# SAST_PCB_V2B_Test_Beta_Sensors.net
KiCad netlist of a schematic drawn in Altium Designer
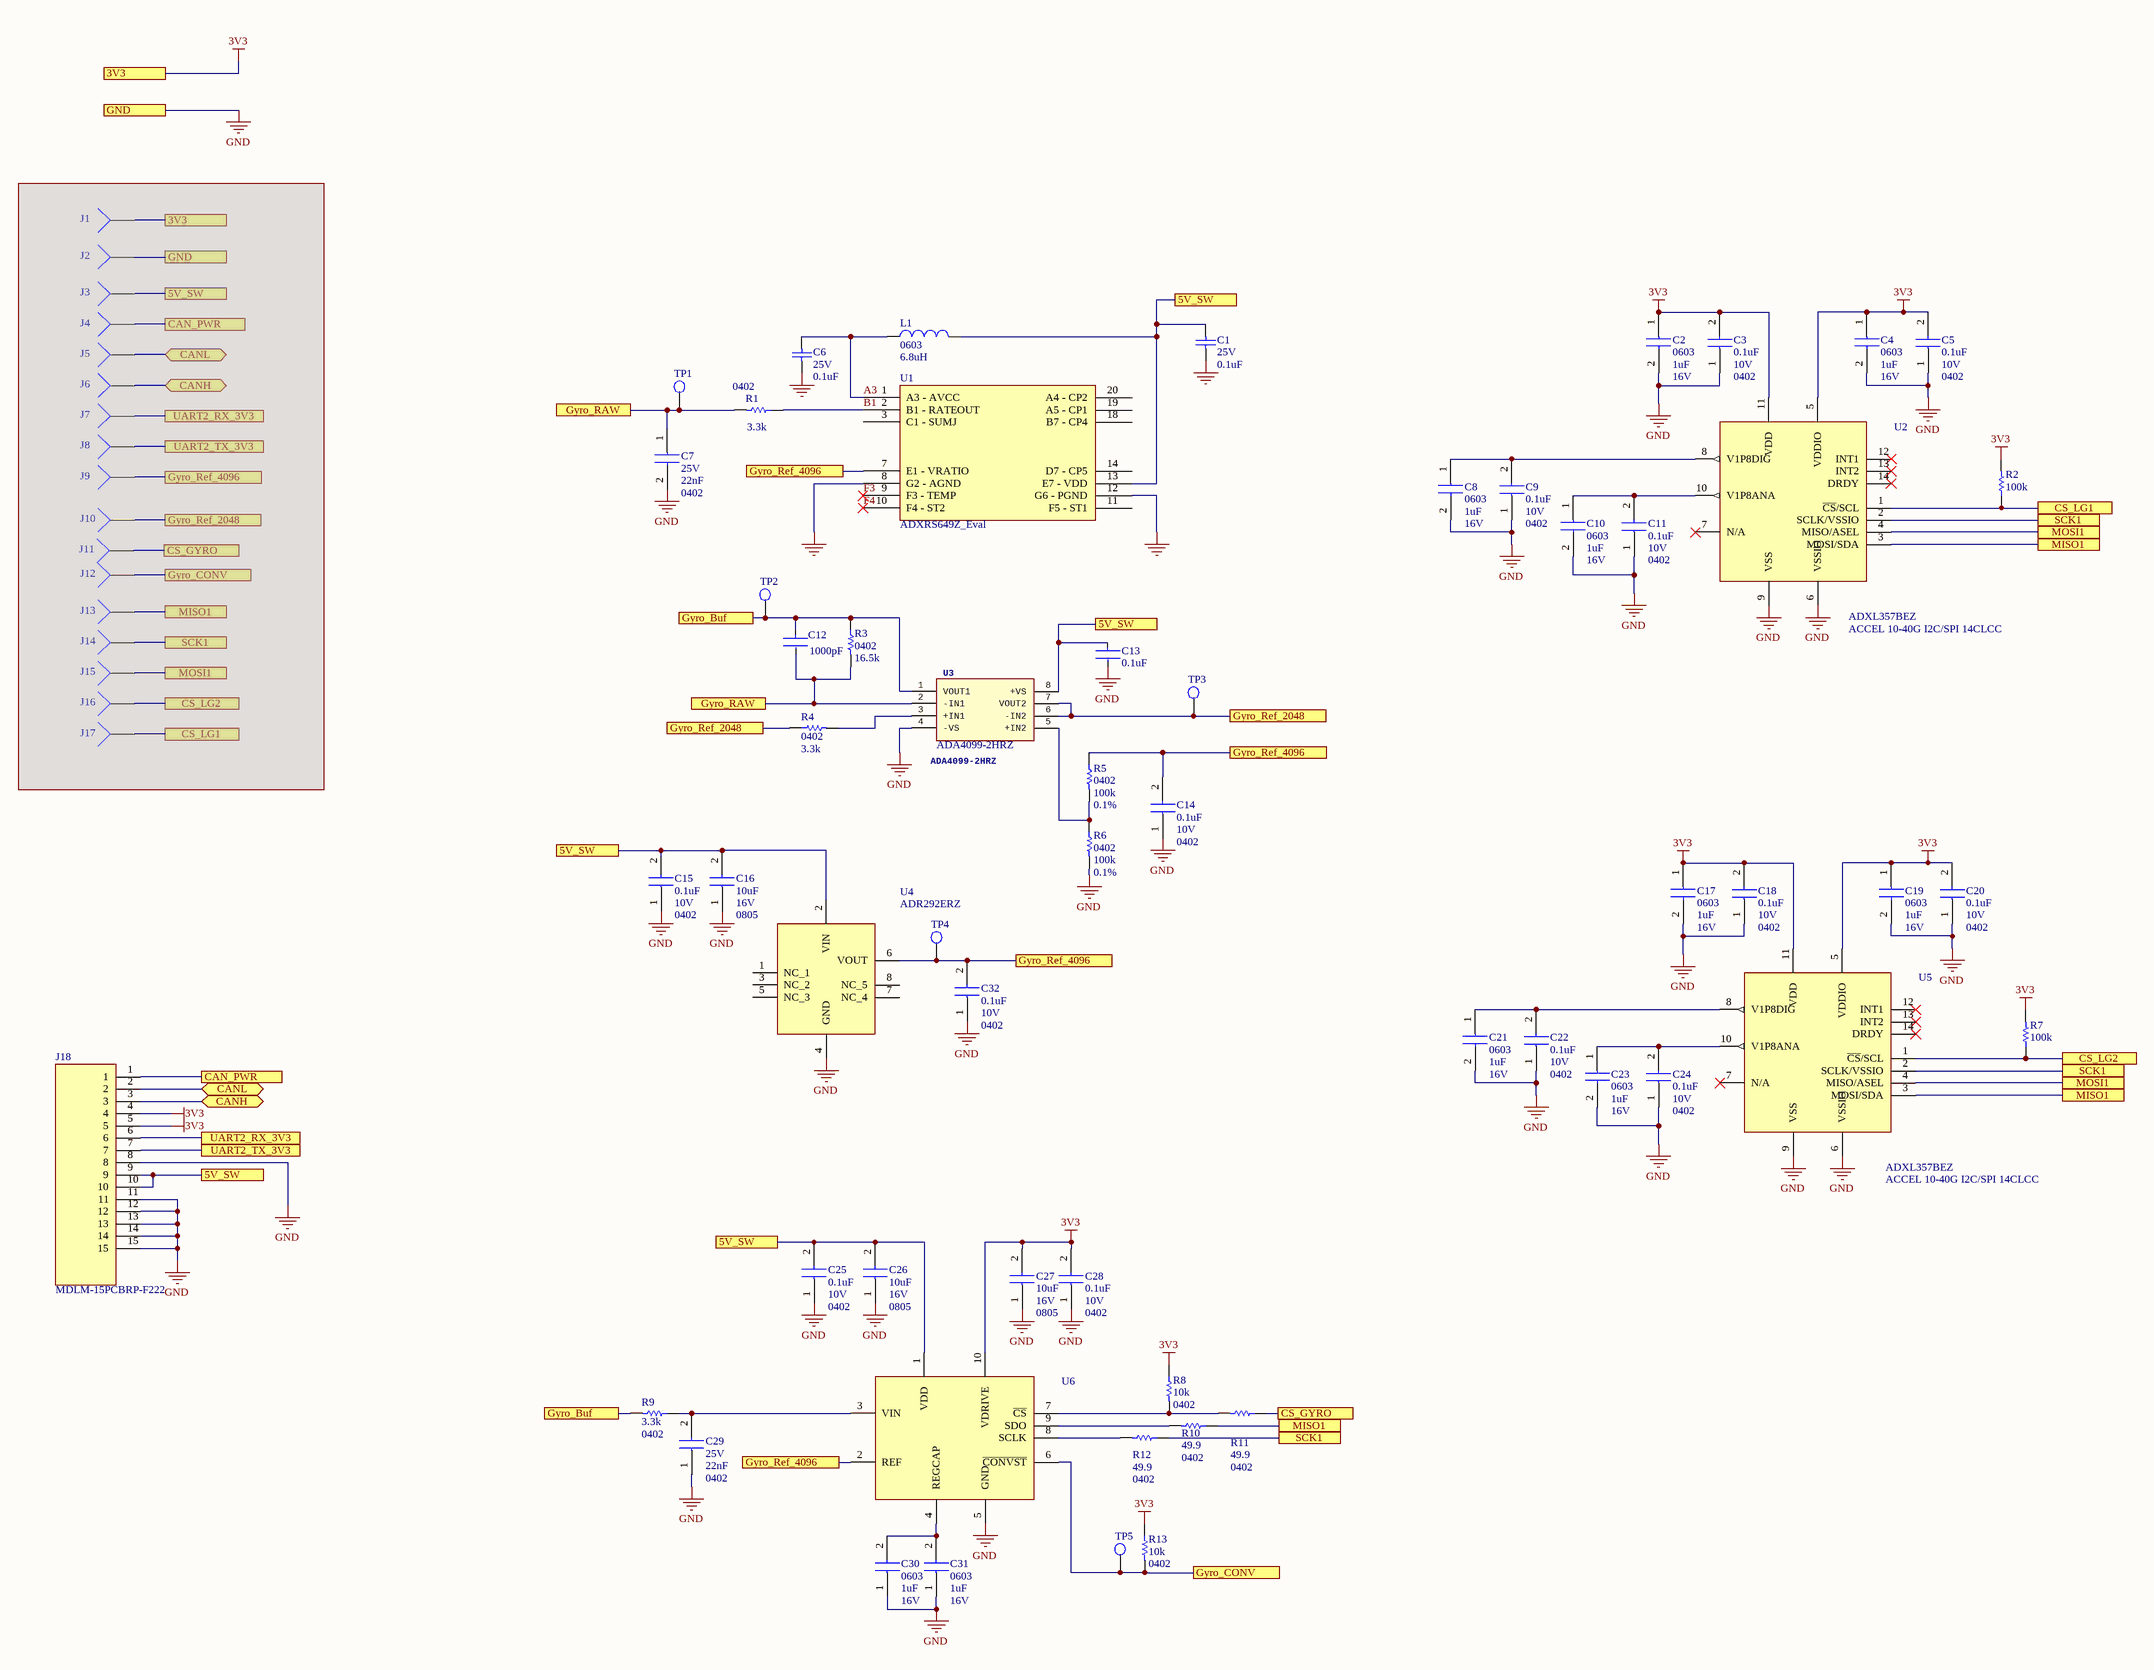
[diagram p0: SAST_PCB_V2B_Test_Beta_Sensors.SchDoc]

(export (version "E")
  (design (tool "Eeschema 10.0.6"))
  (components
    (comp (ref "C1")
      (value "25V")
      (footprint "0402_DSP")
      (description "Capacitor")
      (fields (field (name "ALTIUM_VALUE") "0.1uF") (field (name "PUBLISHER") "Altium Limited"))
      (libsource (lib "Miscellaneous Devices") (part "Cap"))
    )
    (comp (ref "C2")
      (value "1uF")
      (footprint "0603_DSP")
      (description "Capacitor: 1 µF ±10% 16V Ceramic Capacitor X8L 0603")
      (fields
        (field (name "MANUFACTURER_PART_NUMBER") "GCG188L8EE105KA07D")
        (field (name "MOUSER PART NUMBER") "81-GCG188L8EE105KA7D")
        (field (name "CASE/PACKAGE") "0603")
        (field (name "VOLTAGE") "16V")
      )
      (libsource (lib "CS_Library") (part "GCG188L8EE105KA07D"))
    )
    (comp (ref "C3")
      (value "0.1uF")
      (footprint "0402_DSP")
      (description "Capacitor: 0.1 µF ±10% 10V Ceramic Capacitor X8M 0201")
      (fields
        (field (name "MANUFACTURER_PART_NUMBER") "GCM033M8ED104KE07J")
        (field (name "MOUSER PART NUMBER") "81-GCM033M8ED104KE07")
        (field (name "VOLTAGE") "10V")
        (field (name "CASE/PACKAGE") "0402")
      )
      (libsource (lib "CS_Library") (part "GCM033M8ED104KE07J"))
    )
    (comp (ref "C4")
      (value "1uF")
      (footprint "0603_DSP")
      (description "Capacitor: 1 µF ±10% 16V Ceramic Capacitor X8L 0603")
      (fields
        (field (name "MANUFACTURER_PART_NUMBER") "GCG188L8EE105KA07D")
        (field (name "MOUSER PART NUMBER") "81-GCG188L8EE105KA7D")
        (field (name "CASE/PACKAGE") "0603")
        (field (name "VOLTAGE") "16V")
      )
      (libsource (lib "CS_Library") (part "GCG188L8EE105KA07D"))
    )
    (comp (ref "C5")
      (value "0.1uF")
      (footprint "0402_DSP")
      (description "Capacitor: 0.1 µF ±10% 10V Ceramic Capacitor X8M 0201")
      (fields
        (field (name "MANUFACTURER_PART_NUMBER") "GCM033M8ED104KE07J")
        (field (name "MOUSER PART NUMBER") "81-GCM033M8ED104KE07")
        (field (name "VOLTAGE") "10V")
        (field (name "CASE/PACKAGE") "0402")
      )
      (libsource (lib "CS_Library") (part "GCM033M8ED104KE07J"))
    )
    (comp (ref "C6")
      (value "25V")
      (footprint "0402_DSP")
      (description "Capacitor")
      (fields (field (name "ALTIUM_VALUE") "0.1uF") (field (name "PUBLISHER") "Altium Limited"))
      (libsource (lib "Miscellaneous Devices") (part "Cap"))
    )
    (comp (ref "C7")
      (value "22nF")
      (footprint "CS_Library:0402_DSP")
      (description "Capacitor: 0.022 µF ±10% 25V Ceramic Capacitor X8R 0402 (1005 Metric)")
      (fields
        (field (name "MANUFACTURER_PART_NUMBER") "C1005X8R1E223K050BB")
        (field (name "VOLTAGE") "25V")
        (field (name "CASE/PACKAGE") "0402")
        (field (name "Comment") "CAP CER 0.022UF 25V X8R 0402")
      )
      (libsource (lib "CS_Library") (part "C1005X8R1E223K050BB"))
    )
    (comp (ref "C8")
      (value "1uF")
      (footprint "0603_DSP")
      (description "Capacitor: 1 µF ±10% 16V Ceramic Capacitor X8L 0603")
      (fields
        (field (name "MANUFACTURER_PART_NUMBER") "GCG188L8EE105KA07D")
        (field (name "MOUSER PART NUMBER") "81-GCG188L8EE105KA7D")
        (field (name "CASE/PACKAGE") "0603")
        (field (name "VOLTAGE") "16V")
      )
      (libsource (lib "CS_Library") (part "GCG188L8EE105KA07D"))
    )
    (comp (ref "C9")
      (value "0.1uF")
      (footprint "0402_DSP")
      (description "Capacitor: 0.1 µF ±10% 10V Ceramic Capacitor X8M 0201")
      (fields
        (field (name "MANUFACTURER_PART_NUMBER") "GCM033M8ED104KE07J")
        (field (name "MOUSER PART NUMBER") "81-GCM033M8ED104KE07")
        (field (name "VOLTAGE") "10V")
        (field (name "CASE/PACKAGE") "0402")
      )
      (libsource (lib "CS_Library") (part "GCM033M8ED104KE07J"))
    )
    (comp (ref "C10")
      (value "1uF")
      (footprint "0603_DSP")
      (description "Capacitor: 1 µF ±10% 16V Ceramic Capacitor X8L 0603")
      (fields
        (field (name "MANUFACTURER_PART_NUMBER") "GCG188L8EE105KA07D")
        (field (name "MOUSER PART NUMBER") "81-GCG188L8EE105KA7D")
        (field (name "CASE/PACKAGE") "0603")
        (field (name "VOLTAGE") "16V")
      )
      (libsource (lib "CS_Library") (part "GCG188L8EE105KA07D"))
    )
    (comp (ref "C11")
      (value "0.1uF")
      (footprint "0402_DSP")
      (description "Capacitor: 0.1 µF ±10% 10V Ceramic Capacitor X8M 0201")
      (fields
        (field (name "MANUFACTURER_PART_NUMBER") "GCM033M8ED104KE07J")
        (field (name "MOUSER PART NUMBER") "81-GCM033M8ED104KE07")
        (field (name "VOLTAGE") "10V")
        (field (name "CASE/PACKAGE") "0402")
      )
      (libsource (lib "CS_Library") (part "GCM033M8ED104KE07J"))
    )
    (comp (ref "C12")
      (value "1000pF")
      (footprint "FP-GCM155-0_05-IPC_B")
      (description "Ceramic Capacitor for Automotive 100nF ±10% 25VDC X8L 0402 Paper T/R")
      (fields (field (name "MANUFACTURER_PART_NUMBER") "GCM155L81E104KE02D") (field (name "VOLTAGE") "25V"))
      (libsource (lib "Altium Content Vault") (part "02cd4be3c70576c341d710602a673aa"))
    )
    (comp (ref "C13")
      (value "0.1uF")
      (footprint "FP-GCM155-0_05-IPC_B")
      (description "Ceramic Capacitor for Automotive 100nF ±10% 25VDC X8L 0402 Paper T/R")
      (fields (field (name "MANUFACTURER_PART_NUMBER") "GCM155L81E104KE02D") (field (name "VOLTAGE") "25V"))
      (libsource (lib "Altium Content Vault") (part "02cd4be3c70576c341d710602a673aa"))
    )
    (comp (ref "C14")
      (value "0.1uF")
      (footprint "0402_DSP")
      (description "Capacitor: 0.1 µF ±10% 10V Ceramic Capacitor X8M 0201")
      (fields
        (field (name "MANUFACTURER_PART_NUMBER") "GCM033M8ED104KE07J")
        (field (name "MOUSER PART NUMBER") "81-GCM033M8ED104KE07")
        (field (name "VOLTAGE") "10V")
        (field (name "CASE/PACKAGE") "0402")
      )
      (libsource (lib "CS_Library") (part "GCM033M8ED104KE07J"))
    )
    (comp (ref "C15")
      (value "0.1uF")
      (footprint "0402_DSP")
      (description "Capacitor: 0.1 µF ±10% 10V Ceramic Capacitor X8M 0201")
      (fields
        (field (name "MANUFACTURER_PART_NUMBER") "GCM033M8ED104KE07J")
        (field (name "MOUSER PART NUMBER") "81-GCM033M8ED104KE07")
        (field (name "VOLTAGE") "10V")
        (field (name "CASE/PACKAGE") "0402")
      )
      (libsource (lib "CS_Library") (part "GCM033M8ED104KE07J"))
    )
    (comp (ref "C16")
      (value "10uF")
      (footprint "CS_Library:CAPC2012X140N")
      (description "Capacitor:  10 µF ±10% 16V Ceramic Capacitor X8M 0805 (2012 Metric)")
      (fields
        (field (name "MANUFACTURER_PART_NUMBER") "GCM21BM8EE106KE08L")
        (field (name "MOUSER PART NUMBER") "81-GCM21BM8EE106KE8L")
        (field (name "VOLTAGE") "16V")
        (field (name "CASE/PACKAGE") "0805")
      )
      (libsource (lib "CS_Library") (part "GCM21BM8EE106KE08L"))
    )
    (comp (ref "C17")
      (value "1uF")
      (footprint "0603_DSP")
      (description "Capacitor: 1 µF ±10% 16V Ceramic Capacitor X8L 0603")
      (fields
        (field (name "MANUFACTURER_PART_NUMBER") "GCG188L8EE105KA07D")
        (field (name "MOUSER PART NUMBER") "81-GCG188L8EE105KA7D")
        (field (name "CASE/PACKAGE") "0603")
        (field (name "VOLTAGE") "16V")
      )
      (libsource (lib "CS_Library") (part "GCG188L8EE105KA07D"))
    )
    (comp (ref "C18")
      (value "0.1uF")
      (footprint "0402_DSP")
      (description "Capacitor: 0.1 µF ±10% 10V Ceramic Capacitor X8M 0201")
      (fields
        (field (name "MANUFACTURER_PART_NUMBER") "GCM033M8ED104KE07J")
        (field (name "MOUSER PART NUMBER") "81-GCM033M8ED104KE07")
        (field (name "VOLTAGE") "10V")
        (field (name "CASE/PACKAGE") "0402")
      )
      (libsource (lib "CS_Library") (part "GCM033M8ED104KE07J"))
    )
    (comp (ref "C19")
      (value "1uF")
      (footprint "0603_DSP")
      (description "Capacitor: 1 µF ±10% 16V Ceramic Capacitor X8L 0603")
      (fields
        (field (name "MANUFACTURER_PART_NUMBER") "GCG188L8EE105KA07D")
        (field (name "MOUSER PART NUMBER") "81-GCG188L8EE105KA7D")
        (field (name "CASE/PACKAGE") "0603")
        (field (name "VOLTAGE") "16V")
      )
      (libsource (lib "CS_Library") (part "GCG188L8EE105KA07D"))
    )
    (comp (ref "C20")
      (value "0.1uF")
      (footprint "0402_DSP")
      (description "Capacitor: 0.1 µF ±10% 10V Ceramic Capacitor X8M 0201")
      (fields
        (field (name "MANUFACTURER_PART_NUMBER") "GCM033M8ED104KE07J")
        (field (name "MOUSER PART NUMBER") "81-GCM033M8ED104KE07")
        (field (name "VOLTAGE") "10V")
        (field (name "CASE/PACKAGE") "0402")
      )
      (libsource (lib "CS_Library") (part "GCM033M8ED104KE07J"))
    )
    (comp (ref "C21")
      (value "1uF")
      (footprint "0603_DSP")
      (description "Capacitor: 1 µF ±10% 16V Ceramic Capacitor X8L 0603")
      (fields
        (field (name "MANUFACTURER_PART_NUMBER") "GCG188L8EE105KA07D")
        (field (name "MOUSER PART NUMBER") "81-GCG188L8EE105KA7D")
        (field (name "CASE/PACKAGE") "0603")
        (field (name "VOLTAGE") "16V")
      )
      (libsource (lib "CS_Library") (part "GCG188L8EE105KA07D"))
    )
    (comp (ref "C22")
      (value "0.1uF")
      (footprint "0402_DSP")
      (description "Capacitor: 0.1 µF ±10% 10V Ceramic Capacitor X8M 0201")
      (fields
        (field (name "MANUFACTURER_PART_NUMBER") "GCM033M8ED104KE07J")
        (field (name "MOUSER PART NUMBER") "81-GCM033M8ED104KE07")
        (field (name "VOLTAGE") "10V")
        (field (name "CASE/PACKAGE") "0402")
      )
      (libsource (lib "CS_Library") (part "GCM033M8ED104KE07J"))
    )
    (comp (ref "C23")
      (value "1uF")
      (footprint "0603_DSP")
      (description "Capacitor: 1 µF ±10% 16V Ceramic Capacitor X8L 0603")
      (fields
        (field (name "MANUFACTURER_PART_NUMBER") "GCG188L8EE105KA07D")
        (field (name "MOUSER PART NUMBER") "81-GCG188L8EE105KA7D")
        (field (name "CASE/PACKAGE") "0603")
        (field (name "VOLTAGE") "16V")
      )
      (libsource (lib "CS_Library") (part "GCG188L8EE105KA07D"))
    )
    (comp (ref "C24")
      (value "0.1uF")
      (footprint "0402_DSP")
      (description "Capacitor: 0.1 µF ±10% 10V Ceramic Capacitor X8M 0201")
      (fields
        (field (name "MANUFACTURER_PART_NUMBER") "GCM033M8ED104KE07J")
        (field (name "MOUSER PART NUMBER") "81-GCM033M8ED104KE07")
        (field (name "VOLTAGE") "10V")
        (field (name "CASE/PACKAGE") "0402")
      )
      (libsource (lib "CS_Library") (part "GCM033M8ED104KE07J"))
    )
    (comp (ref "C25")
      (value "0.1uF")
      (footprint "0402_DSP")
      (description "Capacitor: 0.1 µF ±10% 10V Ceramic Capacitor X8M 0201")
      (fields
        (field (name "MANUFACTURER_PART_NUMBER") "GCM033M8ED104KE07J")
        (field (name "MOUSER PART NUMBER") "81-GCM033M8ED104KE07")
        (field (name "VOLTAGE") "10V")
        (field (name "CASE/PACKAGE") "0402")
      )
      (libsource (lib "CS_Library") (part "GCM033M8ED104KE07J"))
    )
    (comp (ref "C26")
      (value "10uF")
      (footprint "CS_Library:CAPC2012X140N")
      (description "Capacitor:  10 µF ±10% 16V Ceramic Capacitor X8M 0805 (2012 Metric)")
      (fields
        (field (name "MANUFACTURER_PART_NUMBER") "GCM21BM8EE106KE08L")
        (field (name "MOUSER PART NUMBER") "81-GCM21BM8EE106KE8L")
        (field (name "VOLTAGE") "16V")
        (field (name "CASE/PACKAGE") "0805")
      )
      (libsource (lib "CS_Library") (part "GCM21BM8EE106KE08L"))
    )
    (comp (ref "C27")
      (value "10uF")
      (footprint "CS_Library:CAPC2012X140N")
      (description "Capacitor:  10 µF ±10% 16V Ceramic Capacitor X8M 0805 (2012 Metric)")
      (fields
        (field (name "MANUFACTURER_PART_NUMBER") "GCM21BM8EE106KE08L")
        (field (name "MOUSER PART NUMBER") "81-GCM21BM8EE106KE8L")
        (field (name "VOLTAGE") "16V")
        (field (name "CASE/PACKAGE") "0805")
      )
      (libsource (lib "CS_Library") (part "GCM21BM8EE106KE08L"))
    )
    (comp (ref "C28")
      (value "0.1uF")
      (footprint "0402_DSP")
      (description "Capacitor: 0.1 µF ±10% 10V Ceramic Capacitor X8M 0201")
      (fields
        (field (name "MANUFACTURER_PART_NUMBER") "GCM033M8ED104KE07J")
        (field (name "MOUSER PART NUMBER") "81-GCM033M8ED104KE07")
        (field (name "VOLTAGE") "10V")
        (field (name "CASE/PACKAGE") "0402")
      )
      (libsource (lib "CS_Library") (part "GCM033M8ED104KE07J"))
    )
    (comp (ref "C29")
      (value "22nF")
      (footprint "CS_Library:0402_DSP")
      (description "Capacitor: 0.022 µF ±10% 25V Ceramic Capacitor X8R 0402 (1005 Metric)")
      (fields
        (field (name "MANUFACTURER_PART_NUMBER") "C1005X8R1E223K050BB")
        (field (name "VOLTAGE") "25V")
        (field (name "CASE/PACKAGE") "0402")
        (field (name "Comment") "CAP CER 0.022UF 25V X8R 0402")
      )
      (libsource (lib "CS_Library") (part "C1005X8R1E223K050BB"))
    )
    (comp (ref "C30")
      (value "1uF")
      (footprint "0603_DSP")
      (description "Capacitor: 1 µF ±10% 16V Ceramic Capacitor X8L 0603")
      (fields
        (field (name "MANUFACTURER_PART_NUMBER") "GCG188L8EE105KA07D")
        (field (name "MOUSER PART NUMBER") "81-GCG188L8EE105KA7D")
        (field (name "CASE/PACKAGE") "0603")
        (field (name "VOLTAGE") "16V")
      )
      (libsource (lib "CS_Library") (part "GCG188L8EE105KA07D"))
    )
    (comp (ref "C31")
      (value "1uF")
      (footprint "0603_DSP")
      (description "Capacitor: 1 µF ±10% 16V Ceramic Capacitor X8L 0603")
      (fields
        (field (name "MANUFACTURER_PART_NUMBER") "GCG188L8EE105KA07D")
        (field (name "MOUSER PART NUMBER") "81-GCG188L8EE105KA7D")
        (field (name "CASE/PACKAGE") "0603")
        (field (name "VOLTAGE") "16V")
      )
      (libsource (lib "CS_Library") (part "GCG188L8EE105KA07D"))
    )
    (comp (ref "C32")
      (value "0.1uF")
      (footprint "0402_DSP")
      (description "Capacitor: 0.1 µF ±10% 10V Ceramic Capacitor X8M 0201")
      (fields
        (field (name "MANUFACTURER_PART_NUMBER") "GCM033M8ED104KE07J")
        (field (name "MOUSER PART NUMBER") "81-GCM033M8ED104KE07")
        (field (name "VOLTAGE") "10V")
        (field (name "CASE/PACKAGE") "0402")
      )
      (libsource (lib "CS_Library") (part "GCM033M8ED104KE07J"))
    )
    (comp (ref "J1")
      (value "~")
      (footprint "Wire24Awg2x1HPAD")
      (description "Socket")
      (fields (field (name "PUBLISHER") "Altium Limited"))
      (libsource (lib "Miscellaneous Connectors") (part "Socket"))
    )
    (comp (ref "J2")
      (value "~")
      (footprint "Wire24Awg2x1HPAD")
      (description "Socket")
      (fields (field (name "PUBLISHER") "Altium Limited"))
      (libsource (lib "Miscellaneous Connectors") (part "Socket"))
    )
    (comp (ref "J3")
      (value "~")
      (footprint "Wire24Awg2x1HPAD")
      (description "Socket")
      (fields (field (name "PUBLISHER") "Altium Limited"))
      (libsource (lib "Miscellaneous Connectors") (part "Socket"))
    )
    (comp (ref "J4")
      (value "~")
      (footprint "Wire24Awg2x1HPAD")
      (description "Socket")
      (fields (field (name "PUBLISHER") "Altium Limited"))
      (libsource (lib "Miscellaneous Connectors") (part "Socket"))
    )
    (comp (ref "J5")
      (value "~")
      (footprint "Wire24Awg2x1HPAD")
      (description "Socket")
      (fields (field (name "PUBLISHER") "Altium Limited"))
      (libsource (lib "Miscellaneous Connectors") (part "Socket"))
    )
    (comp (ref "J6")
      (value "~")
      (footprint "Wire24Awg2x1HPAD")
      (description "Socket")
      (fields (field (name "PUBLISHER") "Altium Limited"))
      (libsource (lib "Miscellaneous Connectors") (part "Socket"))
    )
    (comp (ref "J7")
      (value "~")
      (footprint "Wire24Awg2x1HPAD")
      (description "Socket")
      (fields (field (name "PUBLISHER") "Altium Limited"))
      (libsource (lib "Miscellaneous Connectors") (part "Socket"))
    )
    (comp (ref "J8")
      (value "~")
      (footprint "Wire24Awg2x1HPAD")
      (description "Socket")
      (fields (field (name "PUBLISHER") "Altium Limited"))
      (libsource (lib "Miscellaneous Connectors") (part "Socket"))
    )
    (comp (ref "J9")
      (value "~")
      (footprint "Wire24Awg2x1HPAD")
      (description "Socket")
      (fields (field (name "PUBLISHER") "Altium Limited"))
      (libsource (lib "Miscellaneous Connectors") (part "Socket"))
    )
    (comp (ref "J10")
      (value "~")
      (footprint "Wire24Awg2x1HPAD")
      (description "Socket")
      (fields (field (name "PUBLISHER") "Altium Limited"))
      (libsource (lib "Miscellaneous Connectors") (part "Socket"))
    )
    (comp (ref "J11")
      (value "~")
      (footprint "Wire24Awg2x1HPAD")
      (description "Socket")
      (fields (field (name "PUBLISHER") "Altium Limited"))
      (libsource (lib "Miscellaneous Connectors") (part "Socket"))
    )
    (comp (ref "J12")
      (value "~")
      (footprint "Wire24Awg2x1HPAD")
      (description "Socket")
      (fields (field (name "PUBLISHER") "Altium Limited"))
      (libsource (lib "Miscellaneous Connectors") (part "Socket"))
    )
    (comp (ref "J13")
      (value "~")
      (footprint "Wire24Awg2x1HPAD")
      (description "Socket")
      (fields (field (name "PUBLISHER") "Altium Limited"))
      (libsource (lib "Miscellaneous Connectors") (part "Socket"))
    )
    (comp (ref "J14")
      (value "~")
      (footprint "Wire24Awg2x1HPAD")
      (description "Socket")
      (fields (field (name "PUBLISHER") "Altium Limited"))
      (libsource (lib "Miscellaneous Connectors") (part "Socket"))
    )
    (comp (ref "J15")
      (value "~")
      (footprint "Wire24Awg2x1HPAD")
      (description "Socket")
      (fields (field (name "PUBLISHER") "Altium Limited"))
      (libsource (lib "Miscellaneous Connectors") (part "Socket"))
    )
    (comp (ref "J16")
      (value "~")
      (footprint "Wire24Awg2x1HPAD")
      (description "Socket")
      (fields (field (name "PUBLISHER") "Altium Limited"))
      (libsource (lib "Miscellaneous Connectors") (part "Socket"))
    )
    (comp (ref "J17")
      (value "~")
      (footprint "Wire24Awg2x1HPAD")
      (description "Socket")
      (fields (field (name "PUBLISHER") "Altium Limited"))
      (libsource (lib "Miscellaneous Connectors") (part "Socket"))
    )
    (comp (ref "J18")
      (value "MDLM-15PCBRP-F222")
      (footprint "MDLM-15PCBRP-F222")
      (description "Connector")
      (libsource (lib "CS_Library") (part "MDLM-15PCBRP-F222"))
    )
    (comp (ref "L1")
      (value "6.8uH")
      (footprint "0603_DSP")
      (description "Inductor")
      (fields (field (name "PACKAGEREFERENCE") "0603") (field (name "PUBLISHER") "Altium Limited"))
      (libsource (lib "Miscellaneous Devices") (part "Inductor"))
    )
    (comp (ref "R1")
      (value "3.3k")
      (footprint "0402_DSP")
      (fields
        (field (name "MANUFACTURER_PART_NUMBER") "CRCW04023K30FKEDC")
        (field (name "CASE/PACKAGE") "0402")
      )
      (libsource (lib "CS_Library") (part "Resistor 0402"))
    )
    (comp (ref "R2")
      (value "100k")
      (footprint "0402_DSP")
      (fields (field (name "MANUFACTURER_PART_NUMBER") "CRCW0402100KFKEDC"))
      (libsource (lib "CS_Library") (part "Resistor 0402"))
    )
    (comp (ref "R3")
      (value "0402")
      (footprint "0402_DSP")
      (fields
        (field (name "MANUFACTURER_PART_NUMBER") "CRCW04023K30FKEDC")
        (field (name "ALTIUM_VALUE") "16.5k")
      )
      (libsource (lib "CS_Library") (part "Resistor 0402"))
    )
    (comp (ref "R4")
      (value "0402")
      (footprint "0402_DSP")
      (description "Resistor")
      (fields (field (name "ALTIUM_VALUE") "3.3k") (field (name "PUBLISHER") "Altium Limited"))
      (libsource (lib "Miscellaneous Devices") (part "Res1"))
    )
    (comp (ref "R5")
      (value "0402")
      (footprint "0402_DSP")
      (fields (field (name "ALTIUM_VALUE") "100k") (field (name "TOLERANCE") "0.1%"))
      (libsource (lib "CS_Library") (part "Resistor 0402"))
    )
    (comp (ref "R6")
      (value "0402")
      (footprint "0402_DSP")
      (fields (field (name "ALTIUM_VALUE") "100k") (field (name "TOLERANCE") "0.1%"))
      (libsource (lib "CS_Library") (part "Resistor 0402"))
    )
    (comp (ref "R7")
      (value "100k")
      (footprint "0402_DSP")
      (fields (field (name "MANUFACTURER_PART_NUMBER") "CRCW0402100KFKEDC"))
      (libsource (lib "CS_Library") (part "Resistor 0402"))
    )
    (comp (ref "R8")
      (value "10k")
      (footprint "0402_DSP")
      (fields
        (field (name "MANUFACTURER_PART_NUMBER") "CRCW040210K0FKEDC")
        (field (name "CASE/PACKAGE") "0402")
      )
      (libsource (lib "CS_Library") (part "Resistor 0402"))
    )
    (comp (ref "R9")
      (value "3.3k")
      (footprint "0402_DSP")
      (fields
        (field (name "MANUFACTURER_PART_NUMBER") "CRCW04023K30FKEDC")
        (field (name "CASE/PACKAGE") "0402")
      )
      (libsource (lib "CS_Library") (part "Resistor 0402"))
    )
    (comp (ref "R10")
      (value "49.9")
      (footprint "0402_DSP")
      (fields (field (name "CASE/PACKAGE") "0402"))
      (libsource (lib "CS_Library") (part "Resistor 0402"))
    )
    (comp (ref "R11")
      (value "49.9")
      (footprint "0402_DSP")
      (fields (field (name "CASE/PACKAGE") "0402"))
      (libsource (lib "CS_Library") (part "Resistor 0402"))
    )
    (comp (ref "R12")
      (value "49.9")
      (footprint "0402_DSP")
      (fields (field (name "CASE/PACKAGE") "0402"))
      (libsource (lib "CS_Library") (part "Resistor 0402"))
    )
    (comp (ref "R13")
      (value "10k")
      (footprint "0402_DSP")
      (fields
        (field (name "MANUFACTURER_PART_NUMBER") "CRCW040210K0FKEDC")
        (field (name "CASE/PACKAGE") "0402")
      )
      (libsource (lib "CS_Library") (part "Resistor 0402"))
    )
    (comp (ref "TP1")
      (value "~")
      (footprint "TestPoint_4952")
      (fields (field (name "MOUSER_PART_NUMBER") "534-4952"))
      (libsource (lib "CS_Library") (part "Test_Point"))
    )
    (comp (ref "TP2")
      (value "~")
      (footprint "TestPoint_4952")
      (fields (field (name "MOUSER_PART_NUMBER") "534-4952"))
      (libsource (lib "CS_Library") (part "Test_Point"))
    )
    (comp (ref "TP3")
      (value "~")
      (footprint "TestPoint_4952")
      (fields (field (name "MOUSER_PART_NUMBER") "534-4952"))
      (libsource (lib "CS_Library") (part "Test_Point"))
    )
    (comp (ref "TP4")
      (value "~")
      (footprint "TestPoint_4952")
      (fields (field (name "MOUSER_PART_NUMBER") "534-4952"))
      (libsource (lib "CS_Library") (part "Test_Point"))
    )
    (comp (ref "TP5")
      (value "~")
      (footprint "TestPoint_4952")
      (fields (field (name "MOUSER_PART_NUMBER") "534-4952"))
      (libsource (lib "CS_Library") (part "Test_Point"))
    )
    (comp (ref "U1")
      (value "ADXRS649Z_Eval")
      (footprint "ADXRS649Z_Eval")
      (libsource (lib "CS_Library") (part "ADXRS649Z_Eval"))
    )
    (comp (ref "U2")
      (value "ACCEL 10-40G I2C/SPI 14CLCC")
      (footprint "CS_Library:ADXL355BEZ")
      (description "Integrated Circuit:Accelerometer X, Y, Z Axis ±10g, ±20g, ±40g 1Hz ~ 1kHz 14-CLCC (6x6)")
      (fields
        (field (name "MANUFACTURER_PART_NUMBER") "ADXL357BEZ")
        (field (name "MOUSER PART NUMBER") "584-ADXL357BEZ")
        (field (name "ARROW PART NUMBER") "ADXL357BEZ")
      )
      (libsource (lib "CS_Library") (part "ADXL357BEZ"))
    )
    (comp (ref "U3")
      (value "ADA4099-2HRZ")
      (footprint "SOIC127P600X175-8N")
      (fields (field (name "LIBRARYNAME") "ADA4099-2HRZ"))
      (libsource (lib "ADA4099-2HRZ") (part "ADA4099-2HRZ"))
    )
    (comp (ref "U4")
      (value "ADR292ERZ")
      (footprint "CS_Library:SOIC127P600X175-8N")
      (description "Voltage Reference 4.096V, (input min 4.4V)")
      (fields (field (name "MOUSER PART NUMBER") "584-ADR292ERZ"))
      (libsource (lib "CS_Library") (part "ADR292ERZ"))
    )
    (comp (ref "U5")
      (value "ACCEL 10-40G I2C/SPI 14CLCC")
      (footprint "CS_Library:ADXL355BEZ")
      (description "Integrated Circuit:Accelerometer X, Y, Z Axis ±10g, ±20g, ±40g 1Hz ~ 1kHz 14-CLCC (6x6)")
      (fields
        (field (name "MANUFACTURER_PART_NUMBER") "ADXL357BEZ")
        (field (name "MOUSER PART NUMBER") "584-ADXL357BEZ")
        (field (name "ARROW PART NUMBER") "ADXL357BEZ")
      )
      (libsource (lib "CS_Library") (part "ADXL357BEZ"))
    )
    (comp (ref "U6")
      (value "IC ADC 12BIT SAR 10MSOP")
      (footprint "CS_Library:SOP50P490X110-10N")
      (description "Integrated Circuit:12 Bit Analog to Digital Converter 1 Input 1 SAR 10-MSOP")
      (fields
        (field (name "MANUFACTURER_PART_NUMBER") "AD7091RBRMZ")
        (field (name "MOUSER PART NUMBER") "584-AD7091RBRMZ")
      )
      (libsource (lib "CS_Library") (part "AD7091RBRMZ"))
    )
  )
  (nets
    (net (code "1") (name "/5V_SW") (class "Default")
      (node (ref "C1") (pin "2") (pinfunction "2_2") (pintype "passive"))
      (node (ref "C13") (pin "1") (pinfunction "1_1") (pintype "passive"))
      (node (ref "C15") (pin "2") (pinfunction "2_2") (pintype "passive"))
      (node (ref "C16") (pin "2") (pinfunction "2_2") (pintype "passive"))
      (node (ref "C25") (pin "2") (pinfunction "2_2") (pintype "passive"))
      (node (ref "C26") (pin "2") (pinfunction "2_2") (pintype "passive"))
      (node (ref "J18") (pin "10") (pinfunction "10_10") (pintype "passive"))
      (node (ref "J18") (pin "9") (pinfunction "9_9") (pintype "passive"))
      (node (ref "J3") (pin "1") (pinfunction "1_1") (pintype "passive"))
      (node (ref "L1") (pin "2") (pinfunction "2_2") (pintype "passive"))
      (node (ref "U1") (pin "13") (pinfunction "E7_-_VDD_13") (pintype "passive"))
      (node (ref "U3") (pin "8") (pinfunction "+VS_8") (pintype "passive"))
      (node (ref "U4") (pin "2") (pinfunction "VIN_2") (pintype "passive"))
      (node (ref "U6") (pin "1") (pinfunction "VDD_1") (pintype "passive"))
    )
    (net (code "2") (name "/A3") (class "Default")
      (node (ref "C6") (pin "2") (pinfunction "2_2") (pintype "passive"))
      (node (ref "L1") (pin "1") (pinfunction "1_1") (pintype "passive"))
      (node (ref "U1") (pin "1") (pinfunction "A3_-_AVCC_1") (pintype "passive"))
    )
    (net (code "3") (name "/B1") (class "Default")
      (node (ref "R1") (pin "1") (pinfunction "1_1") (pintype "passive"))
      (node (ref "U1") (pin "2") (pinfunction "B1_-_RATEOUT_2") (pintype "passive"))
    )
    (net (code "4") (name "/CANH") (class "Default")
      (node (ref "J18") (pin "3") (pinfunction "3_3") (pintype "passive"))
      (node (ref "J6") (pin "1") (pinfunction "1_1") (pintype "passive"))
    )
    (net (code "5") (name "/CANL") (class "Default")
      (node (ref "J18") (pin "2") (pinfunction "2_2") (pintype "passive"))
      (node (ref "J5") (pin "1") (pinfunction "1_1") (pintype "passive"))
    )
    (net (code "6") (name "/CAN_PWR") (class "Default")
      (node (ref "J18") (pin "1") (pinfunction "1_1") (pintype "passive"))
      (node (ref "J4") (pin "1") (pinfunction "1_1") (pintype "passive"))
    )
    (net (code "7") (name "/CS_GYRO") (class "Default")
      (node (ref "J11") (pin "1") (pinfunction "1_1") (pintype "passive"))
      (node (ref "R11") (pin "1") (pinfunction "1_1") (pintype "passive"))
    )
    (net (code "8") (name "/CS_LG1") (class "Default")
      (node (ref "J17") (pin "1") (pinfunction "1_1") (pintype "passive"))
      (node (ref "R2") (pin "1") (pinfunction "1_1") (pintype "passive"))
      (node (ref "U2") (pin "1") (pinfunction "~{CS}/SCL_1") (pintype "passive"))
    )
    (net (code "9") (name "/CS_LG2") (class "Default")
      (node (ref "J16") (pin "1") (pinfunction "1_1") (pintype "passive"))
      (node (ref "R7") (pin "1") (pinfunction "1_1") (pintype "passive"))
      (node (ref "U5") (pin "1") (pinfunction "~{CS}/SCL_1") (pintype "passive"))
    )
    (net (code "10") (name "/F3") (class "Default")
      (node (ref "U1") (pin "9") (pinfunction "F3_-_TEMP_9") (pintype "passive+no_connect"))
    )
    (net (code "11") (name "/F4") (class "Default")
      (node (ref "U1") (pin "10") (pinfunction "F4_-_ST2_10") (pintype "passive+no_connect"))
    )
    (net (code "12") (name "/Gyro_Buf") (class "Default")
      (node (ref "C12") (pin "1") (pinfunction "1_1") (pintype "passive"))
      (node (ref "R3") (pin "1") (pinfunction "1_1") (pintype "passive"))
      (node (ref "R9") (pin "2") (pinfunction "2_2") (pintype "passive"))
      (node (ref "TP2") (pin "1") (pinfunction "1_1") (pintype "passive"))
      (node (ref "U3") (pin "1") (pinfunction "VOUT1_1") (pintype "passive"))
    )
    (net (code "13") (name "/Gyro_CONV") (class "Default")
      (node (ref "J12") (pin "1") (pinfunction "1_1") (pintype "passive"))
      (node (ref "R13") (pin "2") (pinfunction "2_2") (pintype "passive"))
      (node (ref "TP5") (pin "1") (pinfunction "1_1") (pintype "passive"))
      (node (ref "U6") (pin "6") (pinfunction "~{CONVST}_6") (pintype "passive"))
    )
    (net (code "14") (name "/Gyro_RAW") (class "Default")
      (node (ref "C12") (pin "2") (pinfunction "2_2") (pintype "passive"))
      (node (ref "C7") (pin "1") (pinfunction "1_1") (pintype "passive"))
      (node (ref "R1") (pin "2") (pinfunction "2_2") (pintype "passive"))
      (node (ref "R3") (pin "2") (pinfunction "2_2") (pintype "passive"))
      (node (ref "TP1") (pin "1") (pinfunction "1_1") (pintype "passive"))
      (node (ref "U3") (pin "2") (pinfunction "-IN1_2") (pintype "passive"))
    )
    (net (code "15") (name "/Gyro_Ref_2048") (class "Default")
      (node (ref "J10") (pin "1") (pinfunction "1_1") (pintype "passive"))
      (node (ref "R4") (pin "1") (pinfunction "1_1") (pintype "passive"))
      (node (ref "TP3") (pin "1") (pinfunction "1_1") (pintype "passive"))
      (node (ref "U3") (pin "6") (pinfunction "-IN2_6") (pintype "passive"))
      (node (ref "U3") (pin "7") (pinfunction "VOUT2_7") (pintype "passive"))
    )
    (net (code "16") (name "/Gyro_Ref_4096") (class "Default")
      (node (ref "C14") (pin "2") (pinfunction "2_2") (pintype "passive"))
      (node (ref "C32") (pin "2") (pinfunction "2_2") (pintype "passive"))
      (node (ref "J9") (pin "1") (pinfunction "1_1") (pintype "passive"))
      (node (ref "R5") (pin "1") (pinfunction "1_1") (pintype "passive"))
      (node (ref "TP4") (pin "1") (pinfunction "1_1") (pintype "passive"))
      (node (ref "U1") (pin "7") (pinfunction "E1_-_VRATIO_7") (pintype "passive"))
      (node (ref "U4") (pin "6") (pinfunction "VOUT_6") (pintype "passive"))
      (node (ref "U6") (pin "2") (pinfunction "REF_2") (pintype "passive"))
    )
    (net (code "17") (name "/MISO1") (class "Default")
      (node (ref "J13") (pin "1") (pinfunction "1_1") (pintype "passive"))
      (node (ref "R10") (pin "1") (pinfunction "1_1") (pintype "passive"))
      (node (ref "U2") (pin "3") (pinfunction "MOSI/SDA_3") (pintype "passive"))
      (node (ref "U5") (pin "3") (pinfunction "MOSI/SDA_3") (pintype "passive"))
    )
    (net (code "18") (name "/MOSI1") (class "Default")
      (node (ref "J15") (pin "1") (pinfunction "1_1") (pintype "passive"))
      (node (ref "U2") (pin "4") (pinfunction "MISO/ASEL_4") (pintype "passive"))
      (node (ref "U5") (pin "4") (pinfunction "MISO/ASEL_4") (pintype "passive"))
    )
    (net (code "19") (name "/SCK1") (class "Default")
      (node (ref "J14") (pin "1") (pinfunction "1_1") (pintype "passive"))
      (node (ref "R12") (pin "1") (pinfunction "1_1") (pintype "passive"))
      (node (ref "U2") (pin "2") (pinfunction "SCLK/VSSIO_2") (pintype "passive"))
      (node (ref "U5") (pin "2") (pinfunction "SCLK/VSSIO_2") (pintype "passive"))
    )
    (net (code "20") (name "/UART2_RX_3V3") (class "Default")
      (node (ref "J18") (pin "6") (pinfunction "6_6") (pintype "passive"))
      (node (ref "J7") (pin "1") (pinfunction "1_1") (pintype "passive"))
    )
    (net (code "21") (name "/UART2_TX_3V3") (class "Default")
      (node (ref "J18") (pin "7") (pinfunction "7_7") (pintype "passive"))
      (node (ref "J8") (pin "1") (pinfunction "1_1") (pintype "passive"))
    )
    (net (code "22") (name "3V3") (class "Default")
      (node (ref "C17") (pin "1") (pinfunction "1_1") (pintype "passive"))
      (node (ref "C18") (pin "2") (pinfunction "2_2") (pintype "passive"))
      (node (ref "C19") (pin "1") (pinfunction "1_1") (pintype "passive"))
      (node (ref "C2") (pin "1") (pinfunction "1_1") (pintype "passive"))
      (node (ref "C20") (pin "2") (pinfunction "2_2") (pintype "passive"))
      (node (ref "C27") (pin "2") (pinfunction "2_2") (pintype "passive"))
      (node (ref "C28") (pin "2") (pinfunction "2_2") (pintype "passive"))
      (node (ref "C3") (pin "2") (pinfunction "2_2") (pintype "passive"))
      (node (ref "C4") (pin "1") (pinfunction "1_1") (pintype "passive"))
      (node (ref "C5") (pin "2") (pinfunction "2_2") (pintype "passive"))
      (node (ref "J1") (pin "1") (pinfunction "1_1") (pintype "passive"))
      (node (ref "J18") (pin "4") (pinfunction "4_4") (pintype "passive"))
      (node (ref "J18") (pin "5") (pinfunction "5_5") (pintype "passive"))
      (node (ref "R13") (pin "1") (pinfunction "1_1") (pintype "passive"))
      (node (ref "R2") (pin "2") (pinfunction "2_2") (pintype "passive"))
      (node (ref "R7") (pin "2") (pinfunction "2_2") (pintype "passive"))
      (node (ref "R8") (pin "1") (pinfunction "1_1") (pintype "passive"))
      (node (ref "U2") (pin "11") (pinfunction "VDD_11") (pintype "power_in"))
      (node (ref "U2") (pin "5") (pinfunction "VDDIO_5") (pintype "power_in"))
      (node (ref "U5") (pin "11") (pinfunction "VDD_11") (pintype "power_in"))
      (node (ref "U5") (pin "5") (pinfunction "VDDIO_5") (pintype "power_in"))
      (node (ref "U6") (pin "10") (pinfunction "VDRIVE_10") (pintype "passive"))
    )
    (net (code "23") (name "GND") (class "Default")
      (node (ref "C1") (pin "1") (pinfunction "1_1") (pintype "passive"))
      (node (ref "C10") (pin "2") (pinfunction "2_2") (pintype "passive"))
      (node (ref "C11") (pin "1") (pinfunction "1_1") (pintype "passive"))
      (node (ref "C13") (pin "2") (pinfunction "2_2") (pintype "passive"))
      (node (ref "C14") (pin "1") (pinfunction "1_1") (pintype "passive"))
      (node (ref "C15") (pin "1") (pinfunction "1_1") (pintype "passive"))
      (node (ref "C16") (pin "1") (pinfunction "1_1") (pintype "passive"))
      (node (ref "C17") (pin "2") (pinfunction "2_2") (pintype "passive"))
      (node (ref "C18") (pin "1") (pinfunction "1_1") (pintype "passive"))
      (node (ref "C19") (pin "2") (pinfunction "2_2") (pintype "passive"))
      (node (ref "C2") (pin "2") (pinfunction "2_2") (pintype "passive"))
      (node (ref "C20") (pin "1") (pinfunction "1_1") (pintype "passive"))
      (node (ref "C21") (pin "2") (pinfunction "2_2") (pintype "passive"))
      (node (ref "C22") (pin "1") (pinfunction "1_1") (pintype "passive"))
      (node (ref "C23") (pin "2") (pinfunction "2_2") (pintype "passive"))
      (node (ref "C24") (pin "1") (pinfunction "1_1") (pintype "passive"))
      (node (ref "C25") (pin "1") (pinfunction "1_1") (pintype "passive"))
      (node (ref "C26") (pin "1") (pinfunction "1_1") (pintype "passive"))
      (node (ref "C27") (pin "1") (pinfunction "1_1") (pintype "passive"))
      (node (ref "C28") (pin "1") (pinfunction "1_1") (pintype "passive"))
      (node (ref "C29") (pin "1") (pinfunction "1_1") (pintype "passive"))
      (node (ref "C3") (pin "1") (pinfunction "1_1") (pintype "passive"))
      (node (ref "C30") (pin "1") (pinfunction "1_1") (pintype "passive"))
      (node (ref "C31") (pin "1") (pinfunction "1_1") (pintype "passive"))
      (node (ref "C32") (pin "1") (pinfunction "1_1") (pintype "passive"))
      (node (ref "C4") (pin "2") (pinfunction "2_2") (pintype "passive"))
      (node (ref "C5") (pin "1") (pinfunction "1_1") (pintype "passive"))
      (node (ref "C6") (pin "1") (pinfunction "1_1") (pintype "passive"))
      (node (ref "C7") (pin "2") (pinfunction "2_2") (pintype "passive"))
      (node (ref "C8") (pin "2") (pinfunction "2_2") (pintype "passive"))
      (node (ref "C9") (pin "1") (pinfunction "1_1") (pintype "passive"))
      (node (ref "J18") (pin "11") (pinfunction "11_11") (pintype "passive"))
      (node (ref "J18") (pin "12") (pinfunction "12_12") (pintype "passive"))
      (node (ref "J18") (pin "13") (pinfunction "13_13") (pintype "passive"))
      (node (ref "J18") (pin "14") (pinfunction "14_14") (pintype "passive"))
      (node (ref "J18") (pin "15") (pinfunction "15_15") (pintype "passive"))
      (node (ref "J18") (pin "8") (pinfunction "8_8") (pintype "passive"))
      (node (ref "J2") (pin "1") (pinfunction "1_1") (pintype "passive"))
      (node (ref "R6") (pin "2") (pinfunction "2_2") (pintype "passive"))
      (node (ref "U1") (pin "12") (pinfunction "G6_-_PGND_12") (pintype "passive"))
      (node (ref "U1") (pin "8") (pinfunction "G2_-_AGND_8") (pintype "passive"))
      (node (ref "U2") (pin "6") (pinfunction "VSSIO_6") (pintype "power_in"))
      (node (ref "U2") (pin "9") (pinfunction "VSS_9") (pintype "power_in"))
      (node (ref "U3") (pin "4") (pinfunction "-VS_4") (pintype "passive"))
      (node (ref "U4") (pin "4") (pinfunction "GND_4") (pintype "passive"))
      (node (ref "U5") (pin "6") (pinfunction "VSSIO_6") (pintype "power_in"))
      (node (ref "U5") (pin "9") (pinfunction "VSS_9") (pintype "power_in"))
      (node (ref "U6") (pin "5") (pinfunction "GND_5") (pintype "passive"))
    )
    (net (code "24") (name "Net-(U2-V1P8ANA)") (class "Default")
      (node (ref "C10") (pin "1") (pinfunction "1_1") (pintype "passive"))
      (node (ref "C11") (pin "2") (pinfunction "2_2") (pintype "passive"))
      (node (ref "U2") (pin "10") (pinfunction "V1P8ANA_10") (pintype "output"))
    )
    (net (code "25") (name "Net-(U2-V1P8DIG)") (class "Default")
      (node (ref "C8") (pin "1") (pinfunction "1_1") (pintype "passive"))
      (node (ref "C9") (pin "2") (pinfunction "2_2") (pintype "passive"))
      (node (ref "U2") (pin "8") (pinfunction "V1P8DIG_8") (pintype "output"))
    )
    (net (code "26") (name "Net-(U3-+IN1)") (class "Default")
      (node (ref "R4") (pin "2") (pinfunction "2_2") (pintype "passive"))
      (node (ref "U3") (pin "3") (pinfunction "+IN1_3") (pintype "passive"))
    )
    (net (code "27") (name "Net-(U3-+IN2)") (class "Default")
      (node (ref "R5") (pin "2") (pinfunction "2_2") (pintype "passive"))
      (node (ref "R6") (pin "1") (pinfunction "1_1") (pintype "passive"))
      (node (ref "U3") (pin "5") (pinfunction "+IN2_5") (pintype "passive"))
    )
    (net (code "28") (name "Net-(U5-V1P8ANA)") (class "Default")
      (node (ref "C23") (pin "1") (pinfunction "1_1") (pintype "passive"))
      (node (ref "C24") (pin "2") (pinfunction "2_2") (pintype "passive"))
      (node (ref "U5") (pin "10") (pinfunction "V1P8ANA_10") (pintype "output"))
    )
    (net (code "29") (name "Net-(U5-V1P8DIG)") (class "Default")
      (node (ref "C21") (pin "1") (pinfunction "1_1") (pintype "passive"))
      (node (ref "C22") (pin "2") (pinfunction "2_2") (pintype "passive"))
      (node (ref "U5") (pin "8") (pinfunction "V1P8DIG_8") (pintype "output"))
    )
    (net (code "30") (name "Net-(U6-REGCAP)") (class "Default")
      (node (ref "C30") (pin "2") (pinfunction "2_2") (pintype "passive"))
      (node (ref "C31") (pin "2") (pinfunction "2_2") (pintype "passive"))
      (node (ref "U6") (pin "4") (pinfunction "REGCAP_4") (pintype "passive"))
    )
    (net (code "31") (name "Net-(U6-SCLK)") (class "Default")
      (node (ref "R12") (pin "2") (pinfunction "2_2") (pintype "passive"))
      (node (ref "U6") (pin "8") (pinfunction "SCLK_8") (pintype "passive"))
    )
    (net (code "32") (name "Net-(U6-SDO)") (class "Default")
      (node (ref "R10") (pin "2") (pinfunction "2_2") (pintype "passive"))
      (node (ref "U6") (pin "9") (pinfunction "SDO_9") (pintype "passive"))
    )
    (net (code "33") (name "Net-(U6-VIN)") (class "Default")
      (node (ref "C29") (pin "2") (pinfunction "2_2") (pintype "passive"))
      (node (ref "R9") (pin "1") (pinfunction "1_1") (pintype "passive"))
      (node (ref "U6") (pin "3") (pinfunction "VIN_3") (pintype "passive"))
    )
    (net (code "34") (name "Net-(U6-~{CS})") (class "Default")
      (node (ref "R11") (pin "2") (pinfunction "2_2") (pintype "passive"))
      (node (ref "R8") (pin "2") (pinfunction "2_2") (pintype "passive"))
      (node (ref "U6") (pin "7") (pinfunction "~{CS}_7") (pintype "passive"))
    )
    (net (code "35") (name "unconnected-(U1-A4_-_CP2-Pad20)") (class "Default")
      (node (ref "U1") (pin "20") (pinfunction "A4_-_CP2_20") (pintype "passive"))
    )
    (net (code "36") (name "unconnected-(U1-A5_-_CP1-Pad19)") (class "Default")
      (node (ref "U1") (pin "19") (pinfunction "A5_-_CP1_19") (pintype "passive"))
    )
    (net (code "37") (name "unconnected-(U1-B7_-_CP4-Pad18)") (class "Default")
      (node (ref "U1") (pin "18") (pinfunction "B7_-_CP4_18") (pintype "passive"))
    )
    (net (code "38") (name "unconnected-(U1-C1_-_SUMJ-Pad3)") (class "Default")
      (node (ref "U1") (pin "3") (pinfunction "C1_-_SUMJ_3") (pintype "passive"))
    )
    (net (code "39") (name "unconnected-(U1-D7_-_CP5-Pad14)") (class "Default")
      (node (ref "U1") (pin "14") (pinfunction "D7_-_CP5_14") (pintype "passive"))
    )
    (net (code "40") (name "unconnected-(U1-F5_-_ST1-Pad11)") (class "Default")
      (node (ref "U1") (pin "11") (pinfunction "F5_-_ST1_11") (pintype "passive"))
    )
    (net (code "41") (name "unconnected-(U2-DRDY-Pad14)") (class "Default")
      (node (ref "U2") (pin "14") (pinfunction "DRDY_14") (pintype "passive+no_connect"))
    )
    (net (code "42") (name "unconnected-(U2-INT1-Pad12)") (class "Default")
      (node (ref "U2") (pin "12") (pinfunction "INT1_12") (pintype "passive+no_connect"))
    )
    (net (code "43") (name "unconnected-(U2-INT2-Pad13)") (class "Default")
      (node (ref "U2") (pin "13") (pinfunction "INT2_13") (pintype "passive+no_connect"))
    )
    (net (code "44") (name "unconnected-(U2-N{slash}A-Pad7)") (class "Default")
      (node (ref "U2") (pin "7") (pinfunction "N/A_7") (pintype "power_in+no_connect"))
    )
    (net (code "45") (name "unconnected-(U4-NC_1-Pad1)") (class "Default")
      (node (ref "U4") (pin "1") (pinfunction "NC_1_1") (pintype "passive"))
    )
    (net (code "46") (name "unconnected-(U4-NC_2-Pad3)") (class "Default")
      (node (ref "U4") (pin "3") (pinfunction "NC_2_3") (pintype "passive"))
    )
    (net (code "47") (name "unconnected-(U4-NC_3-Pad5)") (class "Default")
      (node (ref "U4") (pin "5") (pinfunction "NC_3_5") (pintype "passive"))
    )
    (net (code "48") (name "unconnected-(U4-NC_4-Pad7)") (class "Default")
      (node (ref "U4") (pin "7") (pinfunction "NC_4_7") (pintype "passive"))
    )
    (net (code "49") (name "unconnected-(U4-NC_5-Pad8)") (class "Default")
      (node (ref "U4") (pin "8") (pinfunction "NC_5_8") (pintype "passive"))
    )
    (net (code "50") (name "unconnected-(U5-DRDY-Pad14)") (class "Default")
      (node (ref "U5") (pin "14") (pinfunction "DRDY_14") (pintype "passive+no_connect"))
    )
    (net (code "51") (name "unconnected-(U5-INT1-Pad12)") (class "Default")
      (node (ref "U5") (pin "12") (pinfunction "INT1_12") (pintype "passive+no_connect"))
    )
    (net (code "52") (name "unconnected-(U5-INT2-Pad13)") (class "Default")
      (node (ref "U5") (pin "13") (pinfunction "INT2_13") (pintype "passive+no_connect"))
    )
    (net (code "53") (name "unconnected-(U5-N{slash}A-Pad7)") (class "Default")
      (node (ref "U5") (pin "7") (pinfunction "N/A_7") (pintype "power_in+no_connect"))
    )
  )
)
